# Sheet1.net
KiCad netlist of a schematic drawn in Altium Designer
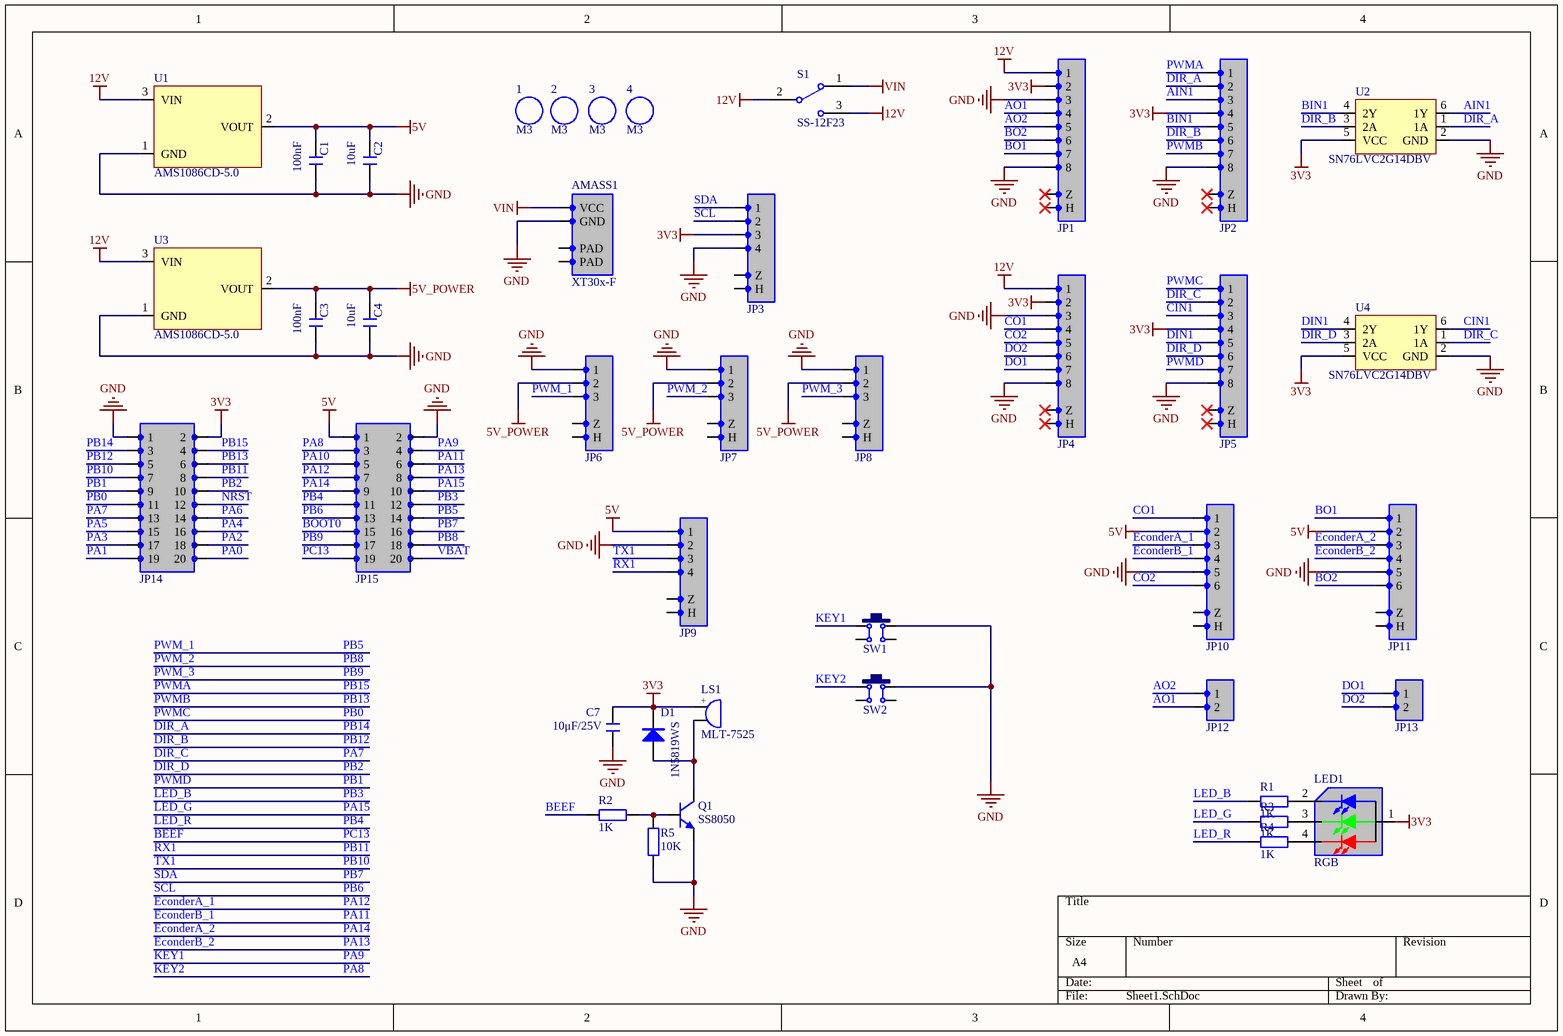
[diagram p0: Sheet1.SchDoc]

(export (version "E")
  (design (tool "Eeschema 10.0.6"))
  (components
    (comp (ref "1")
      (value "M3")
      (footprint "M3 125X200")
      (description "铜柱孔")
      (fields (field (name "版权归属") "源创客"))
      (libsource (lib "13.1-未分类器件") (part "M3"))
    )
    (comp (ref "2")
      (value "M3")
      (footprint "M3 125X200")
      (description "铜柱孔")
      (fields (field (name "版权归属") "源创客"))
      (libsource (lib "13.1-未分类器件") (part "M3"))
    )
    (comp (ref "3")
      (value "M3")
      (footprint "M3 125X200")
      (description "铜柱孔")
      (fields (field (name "版权归属") "源创客"))
      (libsource (lib "13.1-未分类器件") (part "M3"))
    )
    (comp (ref "4")
      (value "M3")
      (footprint "M3 125X200")
      (description "铜柱孔")
      (fields (field (name "版权归属") "源创客"))
      (libsource (lib "13.1-未分类器件") (part "M3"))
    )
    (comp (ref "AMASS1")
      (value "XT30x-F")
      (footprint "XT30U-M")
      (description "Amass防打火电源接口，XT30系列")
      (libsource (lib "SCHLib") (part "XT30"))
    )
    (comp (ref "C1")
      (value "100nF")
      (footprint "C 0603_L")
      (description "无极性贴片电容")
      (fields (field (name "版权归属") "源创客"))
      (libsource (lib "3.2-电容") (part "C"))
    )
    (comp (ref "C2")
      (value "10uF")
      (footprint "C 0603_L")
      (description "无极性贴片电容")
      (fields (field (name "版权归属") "源创客"))
      (libsource (lib "3.2-电容") (part "C"))
    )
    (comp (ref "C3")
      (value "100nF")
      (footprint "C 0603_L")
      (description "无极性贴片电容")
      (fields (field (name "版权归属") "源创客"))
      (libsource (lib "3.2-电容") (part "C"))
    )
    (comp (ref "C4")
      (value "10uF")
      (footprint "C 0603_L")
      (description "无极性贴片电容")
      (fields (field (name "版权归属") "源创客"))
      (libsource (lib "3.2-电容") (part "C"))
    )
    (comp (ref "C7")
      (value "10μF/25V")
      (footprint "C 0603_L")
      (description "无极性贴片电容")
      (fields (field (name "版权归属") "源创客"))
      (libsource (lib "3.2-电容") (part "C"))
    )
    (comp (ref "D1")
      (value "1N5819WS")
      (footprint "SOD-323")
      (description "高速开关二极管")
      (fields (field (name "版权归属") "源创客"))
      (libsource (lib "4.1-二极管") (part "1N4148"))
    )
    (comp (ref "JP1")
      (value "HDR-1X8")
      (footprint "HDR2.54-M-LI-8P")
      (description "8P接插件")
      (fields (field (name "版权归属") "源创客"))
      (libsource (lib "14.6-接插件-脚距2.54") (part "Header 8"))
    )
    (comp (ref "JP2")
      (value "HDR-1X8")
      (footprint "HDR2.54-M-LI-8P")
      (description "8P接插件")
      (fields (field (name "版权归属") "源创客"))
      (libsource (lib "14.6-接插件-脚距2.54") (part "Header 8"))
    )
    (comp (ref "JP3")
      (value "HDR-1X4")
      (footprint "HDR2.54-M-LI-4P")
      (description "4P接插件")
      (fields (field (name "版权归属") "源创客"))
      (libsource (lib "14.6-接插件-脚距2.54") (part "Header 4"))
    )
    (comp (ref "JP4")
      (value "HDR-1X8")
      (footprint "HDR2.54-M-LI-8P")
      (description "8P接插件")
      (fields (field (name "版权归属") "源创客"))
      (libsource (lib "14.6-接插件-脚距2.54") (part "Header 8"))
    )
    (comp (ref "JP5")
      (value "HDR-1X8")
      (footprint "HDR2.54-M-LI-8P")
      (description "8P接插件")
      (fields (field (name "版权归属") "源创客"))
      (libsource (lib "14.6-接插件-脚距2.54") (part "Header 8"))
    )
    (comp (ref "JP6")
      (value "HDR-1X3")
      (footprint "HDR2.54-LI-3P")
      (description "3P接插件")
      (fields (field (name "版权归属") "源创客"))
      (libsource (lib "14.6-接插件-脚距2.54") (part "Header 3"))
    )
    (comp (ref "JP7")
      (value "HDR-1X3")
      (footprint "HDR2.54-LI-3P")
      (description "3P接插件")
      (fields (field (name "版权归属") "源创客"))
      (libsource (lib "14.6-接插件-脚距2.54") (part "Header 3"))
    )
    (comp (ref "JP8")
      (value "HDR-1X3")
      (footprint "HDR2.54-LI-3P")
      (description "3P接插件")
      (fields (field (name "版权归属") "源创客"))
      (libsource (lib "14.6-接插件-脚距2.54") (part "Header 3"))
    )
    (comp (ref "JP9")
      (value "HDR-1X4")
      (footprint "HDR2.54-LI-4P")
      (description "4P接插件")
      (fields (field (name "版权归属") "源创客"))
      (libsource (lib "14.6-接插件-脚距2.54") (part "Header 4"))
    )
    (comp (ref "JP10")
      (value "HDR-1X6")
      (footprint "XH2.54-WI-6P")
      (description "6P接插件")
      (fields (field (name "版权归属") "源创客"))
      (libsource (lib "14.6-接插件-脚距2.54") (part "Header 6"))
    )
    (comp (ref "JP11")
      (value "HDR-1X6")
      (footprint "XH2.54-WI-6P")
      (description "6P接插件")
      (fields (field (name "版权归属") "源创客"))
      (libsource (lib "14.6-接插件-脚距2.54") (part "Header 6"))
    )
    (comp (ref "JP12")
      (value "HDR-1X2")
      (footprint "XH2.54-WI-2P")
      (description "2P接插件")
      (fields (field (name "版权归属") "源创客"))
      (libsource (lib "14.6-接插件-脚距2.54") (part "Header 2"))
    )
    (comp (ref "JP13")
      (value "HDR-1X2")
      (footprint "XH2.54-WI-2P")
      (description "2P接插件")
      (fields (field (name "版权归属") "源创客"))
      (libsource (lib "14.6-接插件-脚距2.54") (part "Header 2"))
    )
    (comp (ref "JP14")
      (value "Header 2X10")
      (footprint "HDR2.54-LI-2x10P")
      (description "10*2P接插件")
      (fields (field (name "版权归属") "源创客"))
      (libsource (lib "14.6-接插件-脚距2.54") (part "Header 10X2"))
    )
    (comp (ref "JP15")
      (value "Header 2X10")
      (footprint "HDR2.54-LI-2x10P")
      (description "10*2P接插件")
      (fields (field (name "版权归属") "源创客"))
      (libsource (lib "14.6-接插件-脚距2.54") (part "Header 10X2"))
    )
    (comp (ref "LED1")
      (value "RGB")
      (footprint "LED 3528-RGB")
      (description "共阳三基色LED")
      (fields (field (name "版权归属") "源创客"))
      (libsource (lib "7.1-LED") (part "LED-RGB-A"))
    )
    (comp (ref "LS1")
      (value "MLT-7525")
      (footprint "BUZZER_7525_S")
      (description "蜂鸣器")
      (fields (field (name "版权归属") "源创客"))
      (libsource (lib "13.1-未分类器件") (part "Buzzer"))
    )
    (comp (ref "Q1")
      (value "SS8050")
      (footprint "SOT23-3L")
      (description "高频放大-NPN型")
      (fields (field (name "版权归属") "源创客"))
      (libsource (lib "5.1-三极管") (part "8050-SMD"))
    )
    (comp (ref "R1")
      (value "1K")
      (footprint "R 0603_L")
      (description "贴片电阻")
      (fields (field (name "版权归属") "源创客"))
      (libsource (lib "3.1-电阻") (part "R"))
    )
    (comp (ref "R2")
      (value "1K")
      (footprint "R 0603_L")
      (description "贴片电阻")
      (fields (field (name "版权归属") "源创客"))
      (libsource (lib "3.1-电阻") (part "R"))
    )
    (comp (ref "R3")
      (value "1K")
      (footprint "R 0603_L")
      (description "贴片电阻")
      (fields (field (name "版权归属") "源创客"))
      (libsource (lib "3.1-电阻") (part "R"))
    )
    (comp (ref "R4")
      (value "1K")
      (footprint "R 0603_L")
      (description "贴片电阻")
      (fields (field (name "版权归属") "源创客"))
      (libsource (lib "3.1-电阻") (part "R"))
    )
    (comp (ref "R5")
      (value "10K")
      (footprint "R 0603_L")
      (description "贴片电阻")
      (fields (field (name "版权归属") "源创客"))
      (libsource (lib "3.1-电阻") (part "R"))
    )
    (comp (ref "S1")
      (value "SS-12F23")
      (footprint "SS-12D10")
      (description "1路拨动开关")
      (fields (field (name "版权归属") "源创客"))
      (libsource (lib "6.2-开关") (part "SSW-1P"))
    )
    (comp (ref "SW1")
      (value "6x6x5")
      (footprint "TSW SMD-3*4*2")
      (description "贴片6x6轻触开关")
      (fields (field (name "版权归属") "源创客"))
      (libsource (lib "6.1-按键") (part "TSW SMD-6x6"))
    )
    (comp (ref "SW2")
      (value "6x6x5")
      (footprint "TSW SMD-3*4*2")
      (description "贴片6x6轻触开关")
      (fields (field (name "版权归属") "源创客"))
      (libsource (lib "6.1-按键") (part "TSW SMD-6x6"))
    )
    (comp (ref "U1")
      (value "AMS1086CD-5.0")
      (footprint "TO252")
      (libsource (lib "Schlib1") (part "AMS1086CD-5.0"))
    )
    (comp (ref "U2")
      (value "SN76LVC2G14DBV")
      (footprint "SOT23-6N")
      (libsource (lib "Schlib1") (part "SN76LVC2G14DBV"))
    )
    (comp (ref "U3")
      (value "AMS1086CD-5.0")
      (footprint "TO252")
      (libsource (lib "Schlib1") (part "AMS1086CD-5.0"))
    )
    (comp (ref "U4")
      (value "SN76LVC2G14DBV")
      (footprint "SOT23-6N")
      (libsource (lib "Schlib1") (part "SN76LVC2G14DBV"))
    )
  )
  (nets
    (net (code "1") (name "/AIN1") (class "Default")
      (node (ref "JP2") (pin "3") (pinfunction "3_3") (pintype "passive"))
      (node (ref "U2") (pin "6") (pinfunction "1Y_6") (pintype "passive"))
    )
    (net (code "2") (name "/AO1") (class "Default")
      (node (ref "JP1") (pin "4") (pinfunction "4_4") (pintype "passive"))
      (node (ref "JP12") (pin "2") (pinfunction "2_2") (pintype "passive"))
    )
    (net (code "3") (name "/AO2") (class "Default")
      (node (ref "JP1") (pin "5") (pinfunction "5_5") (pintype "passive"))
      (node (ref "JP12") (pin "1") (pinfunction "1_1") (pintype "passive"))
    )
    (net (code "4") (name "/BEEF") (class "Default")
      (node (ref "JP15") (pin "19") (pinfunction "19_19") (pintype "passive"))
      (node (ref "R2") (pin "1") (pinfunction "1_1") (pintype "passive"))
    )
    (net (code "5") (name "/BIN1") (class "Default")
      (node (ref "JP2") (pin "5") (pinfunction "5_5") (pintype "passive"))
      (node (ref "U2") (pin "4") (pinfunction "2Y_4") (pintype "passive"))
    )
    (net (code "6") (name "/BO1") (class "Default")
      (node (ref "JP1") (pin "7") (pinfunction "7_7") (pintype "passive"))
      (node (ref "JP11") (pin "1") (pinfunction "1_1") (pintype "passive"))
    )
    (net (code "7") (name "/BO2") (class "Default")
      (node (ref "JP1") (pin "6") (pinfunction "6_6") (pintype "passive"))
      (node (ref "JP11") (pin "6") (pinfunction "6_6") (pintype "passive"))
    )
    (net (code "8") (name "/BOOT0") (class "Default")
      (node (ref "JP15") (pin "15") (pinfunction "15_15") (pintype "passive"))
    )
    (net (code "9") (name "/CIN1") (class "Default")
      (node (ref "JP5") (pin "3") (pinfunction "3_3") (pintype "passive"))
      (node (ref "U4") (pin "6") (pinfunction "1Y_6") (pintype "passive"))
    )
    (net (code "10") (name "/CO1") (class "Default")
      (node (ref "JP10") (pin "1") (pinfunction "1_1") (pintype "passive"))
      (node (ref "JP4") (pin "4") (pinfunction "4_4") (pintype "passive"))
    )
    (net (code "11") (name "/CO2") (class "Default")
      (node (ref "JP10") (pin "6") (pinfunction "6_6") (pintype "passive"))
      (node (ref "JP4") (pin "5") (pinfunction "5_5") (pintype "passive"))
    )
    (net (code "12") (name "/DIN1") (class "Default")
      (node (ref "JP5") (pin "5") (pinfunction "5_5") (pintype "passive"))
      (node (ref "U4") (pin "4") (pinfunction "2Y_4") (pintype "passive"))
    )
    (net (code "13") (name "/DIR_A") (class "Default")
      (node (ref "JP14") (pin "3") (pinfunction "3_3") (pintype "passive"))
      (node (ref "JP2") (pin "2") (pinfunction "2_2") (pintype "passive"))
      (node (ref "U2") (pin "1") (pinfunction "1A_1") (pintype "passive"))
    )
    (net (code "14") (name "/DIR_B") (class "Default")
      (node (ref "JP14") (pin "5") (pinfunction "5_5") (pintype "passive"))
      (node (ref "JP2") (pin "6") (pinfunction "6_6") (pintype "passive"))
      (node (ref "U2") (pin "3") (pinfunction "2A_3") (pintype "passive"))
    )
    (net (code "15") (name "/DIR_C") (class "Default")
      (node (ref "JP14") (pin "13") (pinfunction "13_13") (pintype "passive"))
      (node (ref "JP5") (pin "2") (pinfunction "2_2") (pintype "passive"))
      (node (ref "U4") (pin "1") (pinfunction "1A_1") (pintype "passive"))
    )
    (net (code "16") (name "/DIR_D") (class "Default")
      (node (ref "JP14") (pin "10") (pinfunction "10_10") (pintype "passive"))
      (node (ref "JP5") (pin "6") (pinfunction "6_6") (pintype "passive"))
      (node (ref "U4") (pin "3") (pinfunction "2A_3") (pintype "passive"))
    )
    (net (code "17") (name "/DO1") (class "Default")
      (node (ref "JP13") (pin "1") (pinfunction "1_1") (pintype "passive"))
      (node (ref "JP4") (pin "7") (pinfunction "7_7") (pintype "passive"))
    )
    (net (code "18") (name "/DO2") (class "Default")
      (node (ref "JP13") (pin "2") (pinfunction "2_2") (pintype "passive"))
      (node (ref "JP4") (pin "6") (pinfunction "6_6") (pintype "passive"))
    )
    (net (code "19") (name "/EconderA_1") (class "Default")
      (node (ref "JP10") (pin "3") (pinfunction "3_3") (pintype "passive"))
      (node (ref "JP15") (pin "7") (pinfunction "7_7") (pintype "passive"))
    )
    (net (code "20") (name "/EconderA_2") (class "Default")
      (node (ref "JP11") (pin "3") (pinfunction "3_3") (pintype "passive"))
      (node (ref "JP15") (pin "9") (pinfunction "9_9") (pintype "passive"))
    )
    (net (code "21") (name "/EconderB_1") (class "Default")
      (node (ref "JP10") (pin "4") (pinfunction "4_4") (pintype "passive"))
      (node (ref "JP15") (pin "6") (pinfunction "6_6") (pintype "passive"))
    )
    (net (code "22") (name "/EconderB_2") (class "Default")
      (node (ref "JP11") (pin "4") (pinfunction "4_4") (pintype "passive"))
      (node (ref "JP15") (pin "8") (pinfunction "8_8") (pintype "passive"))
    )
    (net (code "23") (name "/KEY1") (class "Default")
      (node (ref "JP15") (pin "4") (pinfunction "4_4") (pintype "passive"))
      (node (ref "SW1") (pin "1") (pinfunction "1_1") (pintype "passive"))
    )
    (net (code "24") (name "/KEY2") (class "Default")
      (node (ref "JP15") (pin "3") (pinfunction "3_3") (pintype "passive"))
      (node (ref "SW2") (pin "1") (pinfunction "1_1") (pintype "passive"))
    )
    (net (code "25") (name "/LED_B") (class "Default")
      (node (ref "JP15") (pin "12") (pinfunction "12_12") (pintype "passive"))
      (node (ref "R1") (pin "1") (pinfunction "1_1") (pintype "passive"))
    )
    (net (code "26") (name "/LED_G") (class "Default")
      (node (ref "JP15") (pin "10") (pinfunction "10_10") (pintype "passive"))
      (node (ref "R3") (pin "1") (pinfunction "1_1") (pintype "passive"))
    )
    (net (code "27") (name "/LED_R") (class "Default")
      (node (ref "JP15") (pin "11") (pinfunction "11_11") (pintype "passive"))
      (node (ref "R4") (pin "1") (pinfunction "1_1") (pintype "passive"))
    )
    (net (code "28") (name "/NRST") (class "Default")
      (node (ref "JP14") (pin "12") (pinfunction "12_12") (pintype "passive"))
    )
    (net (code "29") (name "/PA0") (class "Default")
      (node (ref "JP14") (pin "20") (pinfunction "20_20") (pintype "passive"))
    )
    (net (code "30") (name "/PA1") (class "Default")
      (node (ref "JP14") (pin "19") (pinfunction "19_19") (pintype "passive"))
    )
    (net (code "31") (name "/PA2") (class "Default")
      (node (ref "JP14") (pin "18") (pinfunction "18_18") (pintype "passive"))
    )
    (net (code "32") (name "/PA3") (class "Default")
      (node (ref "JP14") (pin "17") (pinfunction "17_17") (pintype "passive"))
    )
    (net (code "33") (name "/PA4") (class "Default")
      (node (ref "JP14") (pin "16") (pinfunction "16_16") (pintype "passive"))
    )
    (net (code "34") (name "/PA5") (class "Default")
      (node (ref "JP14") (pin "15") (pinfunction "15_15") (pintype "passive"))
    )
    (net (code "35") (name "/PA6") (class "Default")
      (node (ref "JP14") (pin "14") (pinfunction "14_14") (pintype "passive"))
    )
    (net (code "36") (name "/PA10") (class "Default")
      (node (ref "JP15") (pin "5") (pinfunction "5_5") (pintype "passive"))
    )
    (net (code "37") (name "/PB0") (class "Default")
      (node (ref "JP14") (pin "11") (pinfunction "11_11") (pintype "passive"))
      (node (ref "JP5") (pin "1") (pinfunction "1_1") (pintype "passive"))
    )
    (net (code "38") (name "/PB1") (class "Default")
      (node (ref "JP14") (pin "9") (pinfunction "9_9") (pintype "passive"))
      (node (ref "JP5") (pin "7") (pinfunction "7_7") (pintype "passive"))
    )
    (net (code "39") (name "/PB5") (class "Default")
      (node (ref "JP15") (pin "14") (pinfunction "14_14") (pintype "passive"))
      (node (ref "JP6") (pin "3") (pinfunction "3_3") (pintype "passive"))
    )
    (net (code "40") (name "/PB6") (class "Default")
      (node (ref "JP15") (pin "13") (pinfunction "13_13") (pintype "passive"))
      (node (ref "JP3") (pin "2") (pinfunction "2_2") (pintype "passive"))
    )
    (net (code "41") (name "/PB7") (class "Default")
      (node (ref "JP15") (pin "16") (pinfunction "16_16") (pintype "passive"))
      (node (ref "JP3") (pin "1") (pinfunction "1_1") (pintype "passive"))
    )
    (net (code "42") (name "/PB8") (class "Default")
      (node (ref "JP15") (pin "18") (pinfunction "18_18") (pintype "passive"))
      (node (ref "JP7") (pin "3") (pinfunction "3_3") (pintype "passive"))
    )
    (net (code "43") (name "/PB9") (class "Default")
      (node (ref "JP15") (pin "17") (pinfunction "17_17") (pintype "passive"))
      (node (ref "JP8") (pin "3") (pinfunction "3_3") (pintype "passive"))
    )
    (net (code "44") (name "/PB10") (class "Default")
      (node (ref "JP14") (pin "7") (pinfunction "7_7") (pintype "passive"))
      (node (ref "JP9") (pin "3") (pinfunction "3_3") (pintype "passive"))
    )
    (net (code "45") (name "/PB11") (class "Default")
      (node (ref "JP14") (pin "8") (pinfunction "8_8") (pintype "passive"))
      (node (ref "JP9") (pin "4") (pinfunction "4_4") (pintype "passive"))
    )
    (net (code "46") (name "/PB13") (class "Default")
      (node (ref "JP14") (pin "6") (pinfunction "6_6") (pintype "passive"))
      (node (ref "JP2") (pin "7") (pinfunction "7_7") (pintype "passive"))
    )
    (net (code "47") (name "/PB15") (class "Default")
      (node (ref "JP14") (pin "4") (pinfunction "4_4") (pintype "passive"))
      (node (ref "JP2") (pin "1") (pinfunction "1_1") (pintype "passive"))
    )
    (net (code "48") (name "/VBAT") (class "Default")
      (node (ref "JP15") (pin "20") (pinfunction "20_20") (pintype "passive"))
    )
    (net (code "49") (name "3V3") (class "Default")
      (node (ref "C7") (pin "1") (pinfunction "1_1") (pintype "passive"))
      (node (ref "D1") (pin "2") (pinfunction "K_2") (pintype "passive"))
      (node (ref "JP1") (pin "2") (pinfunction "2_2") (pintype "passive"))
      (node (ref "JP14") (pin "2") (pinfunction "2_2") (pintype "passive"))
      (node (ref "JP2") (pin "4") (pinfunction "4_4") (pintype "passive"))
      (node (ref "JP3") (pin "3") (pinfunction "3_3") (pintype "passive"))
      (node (ref "JP4") (pin "2") (pinfunction "2_2") (pintype "passive"))
      (node (ref "JP5") (pin "4") (pinfunction "4_4") (pintype "passive"))
      (node (ref "LED1") (pin "1") (pintype "passive"))
      (node (ref "LS1") (pin "1") (pinfunction "1_1") (pintype "passive"))
      (node (ref "U2") (pin "5") (pinfunction "VCC_5") (pintype "passive"))
      (node (ref "U4") (pin "5") (pinfunction "VCC_5") (pintype "passive"))
    )
    (net (code "50") (name "5V") (class "Default")
      (node (ref "C1") (pin "1") (pinfunction "1_1") (pintype "passive"))
      (node (ref "C2") (pin "1") (pinfunction "1_1") (pintype "passive"))
      (node (ref "JP10") (pin "2") (pinfunction "2_2") (pintype "passive"))
      (node (ref "JP11") (pin "2") (pinfunction "2_2") (pintype "passive"))
      (node (ref "JP15") (pin "1") (pinfunction "1_1") (pintype "passive"))
      (node (ref "JP9") (pin "1") (pinfunction "1_1") (pintype "passive"))
      (node (ref "U1") (pin "2") (pinfunction "VOUT_2") (pintype "passive"))
    )
    (net (code "51") (name "5V_POWER") (class "Default")
      (node (ref "C3") (pin "1") (pinfunction "1_1") (pintype "passive"))
      (node (ref "C4") (pin "1") (pinfunction "1_1") (pintype "passive"))
      (node (ref "JP6") (pin "2") (pinfunction "2_2") (pintype "passive"))
      (node (ref "JP7") (pin "2") (pinfunction "2_2") (pintype "passive"))
      (node (ref "JP8") (pin "2") (pinfunction "2_2") (pintype "passive"))
      (node (ref "U3") (pin "2") (pinfunction "VOUT_2") (pintype "passive"))
    )
    (net (code "52") (name "12V") (class "Default")
      (node (ref "JP1") (pin "1") (pinfunction "1_1") (pintype "passive"))
      (node (ref "JP4") (pin "1") (pinfunction "1_1") (pintype "passive"))
      (node (ref "S1") (pin "2") (pinfunction "2_2") (pintype "passive"))
      (node (ref "S1") (pin "3") (pinfunction "3_3") (pintype "passive"))
      (node (ref "U1") (pin "3") (pinfunction "VIN_3") (pintype "passive"))
      (node (ref "U3") (pin "3") (pinfunction "VIN_3") (pintype "passive"))
    )
    (net (code "53") (name "GND") (class "Default")
      (node (ref "AMASS1") (pin "2") (pinfunction "GND_2") (pintype "passive"))
      (node (ref "C1") (pin "2") (pinfunction "2_2") (pintype "passive"))
      (node (ref "C2") (pin "2") (pinfunction "2_2") (pintype "passive"))
      (node (ref "C3") (pin "2") (pinfunction "2_2") (pintype "passive"))
      (node (ref "C4") (pin "2") (pinfunction "2_2") (pintype "passive"))
      (node (ref "C7") (pin "2") (pinfunction "2_2") (pintype "passive"))
      (node (ref "JP1") (pin "3") (pinfunction "3_3") (pintype "passive"))
      (node (ref "JP1") (pin "8") (pinfunction "8_8") (pintype "passive"))
      (node (ref "JP10") (pin "5") (pinfunction "5_5") (pintype "passive"))
      (node (ref "JP11") (pin "5") (pinfunction "5_5") (pintype "passive"))
      (node (ref "JP14") (pin "1") (pinfunction "1_1") (pintype "passive"))
      (node (ref "JP15") (pin "2") (pinfunction "2_2") (pintype "passive"))
      (node (ref "JP2") (pin "8") (pinfunction "8_8") (pintype "passive"))
      (node (ref "JP3") (pin "4") (pinfunction "4_4") (pintype "passive"))
      (node (ref "JP4") (pin "3") (pinfunction "3_3") (pintype "passive"))
      (node (ref "JP4") (pin "8") (pinfunction "8_8") (pintype "passive"))
      (node (ref "JP5") (pin "8") (pinfunction "8_8") (pintype "passive"))
      (node (ref "JP6") (pin "1") (pinfunction "1_1") (pintype "passive"))
      (node (ref "JP7") (pin "1") (pinfunction "1_1") (pintype "passive"))
      (node (ref "JP8") (pin "1") (pinfunction "1_1") (pintype "passive"))
      (node (ref "JP9") (pin "2") (pinfunction "2_2") (pintype "passive"))
      (node (ref "Q1") (pin "2") (pinfunction "E_2") (pintype "passive"))
      (node (ref "R5") (pin "2") (pinfunction "2_2") (pintype "passive"))
      (node (ref "SW1") (pin "2") (pinfunction "2_2") (pintype "passive"))
      (node (ref "SW2") (pin "2") (pinfunction "2_2") (pintype "passive"))
      (node (ref "U1") (pin "1") (pinfunction "GND_1") (pintype "passive"))
      (node (ref "U2") (pin "2") (pinfunction "GND_2") (pintype "passive"))
      (node (ref "U3") (pin "1") (pinfunction "GND_1") (pintype "passive"))
      (node (ref "U4") (pin "2") (pinfunction "GND_2") (pintype "passive"))
    )
    (net (code "54") (name "Net-(D1-A)") (class "Default")
      (node (ref "D1") (pin "1") (pinfunction "A_1") (pintype "passive"))
      (node (ref "LS1") (pin "2") (pinfunction "2_2") (pintype "passive"))
      (node (ref "Q1") (pin "3") (pinfunction "C_3") (pintype "passive"))
    )
    (net (code "55") (name "Net-(LED1-Pad2)") (class "Default")
      (node (ref "LED1") (pin "2") (pintype "passive"))
      (node (ref "R1") (pin "2") (pinfunction "2_2") (pintype "passive"))
    )
    (net (code "56") (name "Net-(LED1-Pad3)") (class "Default")
      (node (ref "LED1") (pin "3") (pintype "passive"))
      (node (ref "R3") (pin "2") (pinfunction "2_2") (pintype "passive"))
    )
    (net (code "57") (name "Net-(LED1-Pad4)") (class "Default")
      (node (ref "LED1") (pin "4") (pintype "passive"))
      (node (ref "R4") (pin "2") (pinfunction "2_2") (pintype "passive"))
    )
    (net (code "58") (name "Net-(Q1-B)") (class "Default")
      (node (ref "Q1") (pin "1") (pinfunction "B_1") (pintype "passive"))
      (node (ref "R2") (pin "2") (pinfunction "2_2") (pintype "passive"))
      (node (ref "R5") (pin "1") (pinfunction "1_1") (pintype "passive"))
    )
    (net (code "59") (name "VIN") (class "Default")
      (node (ref "AMASS1") (pin "1") (pinfunction "VCC_1") (pintype "passive"))
      (node (ref "S1") (pin "1") (pinfunction "1_1") (pintype "passive"))
    )
    (net (code "60") (name "unconnected-(AMASS1-PAD-Pad0)") (class "Default")
      (node (ref "AMASS1") (pin "0") (pinfunction "PAD_0") (pintype "passive"))
    )
    (net (code "61") (name "unconnected-(AMASS1-PAD-Pad100)") (class "Default")
      (node (ref "AMASS1") (pin "100") (pinfunction "PAD_100") (pintype "passive"))
    )
    (net (code "62") (name "unconnected-(JP1-H-Pad100)") (class "Default")
      (node (ref "JP1") (pin "100") (pinfunction "H_100") (pintype "passive+no_connect"))
    )
    (net (code "63") (name "unconnected-(JP1-Z-Pad0)") (class "Default")
      (node (ref "JP1") (pin "0") (pinfunction "Z_0") (pintype "passive+no_connect"))
    )
    (net (code "64") (name "unconnected-(JP2-H-Pad100)") (class "Default")
      (node (ref "JP2") (pin "100") (pinfunction "H_100") (pintype "passive+no_connect"))
    )
    (net (code "65") (name "unconnected-(JP2-Z-Pad0)") (class "Default")
      (node (ref "JP2") (pin "0") (pinfunction "Z_0") (pintype "passive+no_connect"))
    )
    (net (code "66") (name "unconnected-(JP3-H-Pad100)") (class "Default")
      (node (ref "JP3") (pin "100") (pinfunction "H_100") (pintype "passive"))
    )
    (net (code "67") (name "unconnected-(JP3-Z-Pad0)") (class "Default")
      (node (ref "JP3") (pin "0") (pinfunction "Z_0") (pintype "passive"))
    )
    (net (code "68") (name "unconnected-(JP4-H-Pad100)") (class "Default")
      (node (ref "JP4") (pin "100") (pinfunction "H_100") (pintype "passive+no_connect"))
    )
    (net (code "69") (name "unconnected-(JP4-Z-Pad0)") (class "Default")
      (node (ref "JP4") (pin "0") (pinfunction "Z_0") (pintype "passive+no_connect"))
    )
    (net (code "70") (name "unconnected-(JP5-H-Pad100)") (class "Default")
      (node (ref "JP5") (pin "100") (pinfunction "H_100") (pintype "passive+no_connect"))
    )
    (net (code "71") (name "unconnected-(JP5-Z-Pad0)") (class "Default")
      (node (ref "JP5") (pin "0") (pinfunction "Z_0") (pintype "passive+no_connect"))
    )
    (net (code "72") (name "unconnected-(JP6-H-Pad100)") (class "Default")
      (node (ref "JP6") (pin "100") (pinfunction "H_100") (pintype "passive"))
    )
    (net (code "73") (name "unconnected-(JP6-Z-Pad0)") (class "Default")
      (node (ref "JP6") (pin "0") (pinfunction "Z_0") (pintype "passive"))
    )
    (net (code "74") (name "unconnected-(JP7-H-Pad100)") (class "Default")
      (node (ref "JP7") (pin "100") (pinfunction "H_100") (pintype "passive"))
    )
    (net (code "75") (name "unconnected-(JP7-Z-Pad0)") (class "Default")
      (node (ref "JP7") (pin "0") (pinfunction "Z_0") (pintype "passive"))
    )
    (net (code "76") (name "unconnected-(JP8-H-Pad100)") (class "Default")
      (node (ref "JP8") (pin "100") (pinfunction "H_100") (pintype "passive"))
    )
    (net (code "77") (name "unconnected-(JP8-Z-Pad0)") (class "Default")
      (node (ref "JP8") (pin "0") (pinfunction "Z_0") (pintype "passive"))
    )
    (net (code "78") (name "unconnected-(JP9-H-Pad100)") (class "Default")
      (node (ref "JP9") (pin "100") (pinfunction "H_100") (pintype "passive"))
    )
    (net (code "79") (name "unconnected-(JP9-Z-Pad0)") (class "Default")
      (node (ref "JP9") (pin "0") (pinfunction "Z_0") (pintype "passive"))
    )
    (net (code "80") (name "unconnected-(JP10-H-Pad100)") (class "Default")
      (node (ref "JP10") (pin "100") (pinfunction "H_100") (pintype "passive"))
    )
    (net (code "81") (name "unconnected-(JP10-Z-Pad0)") (class "Default")
      (node (ref "JP10") (pin "0") (pinfunction "Z_0") (pintype "passive"))
    )
    (net (code "82") (name "unconnected-(JP11-H-Pad100)") (class "Default")
      (node (ref "JP11") (pin "100") (pinfunction "H_100") (pintype "passive"))
    )
    (net (code "83") (name "unconnected-(JP11-Z-Pad0)") (class "Default")
      (node (ref "JP11") (pin "0") (pinfunction "Z_0") (pintype "passive"))
    )
    (net (code "84") (name "unconnected-(SW1-Pad3)") (class "Default")
      (node (ref "SW1") (pin "3") (pinfunction "3_3") (pintype "passive"))
    )
    (net (code "85") (name "unconnected-(SW1-Pad4)") (class "Default")
      (node (ref "SW1") (pin "4") (pinfunction "4_4") (pintype "passive"))
    )
    (net (code "86") (name "unconnected-(SW2-Pad3)") (class "Default")
      (node (ref "SW2") (pin "3") (pinfunction "3_3") (pintype "passive"))
    )
    (net (code "87") (name "unconnected-(SW2-Pad4)") (class "Default")
      (node (ref "SW2") (pin "4") (pinfunction "4_4") (pintype "passive"))
    )
  )
)
